# H41R70.net
KiCad netlist of a schematic drawn in EAGLE
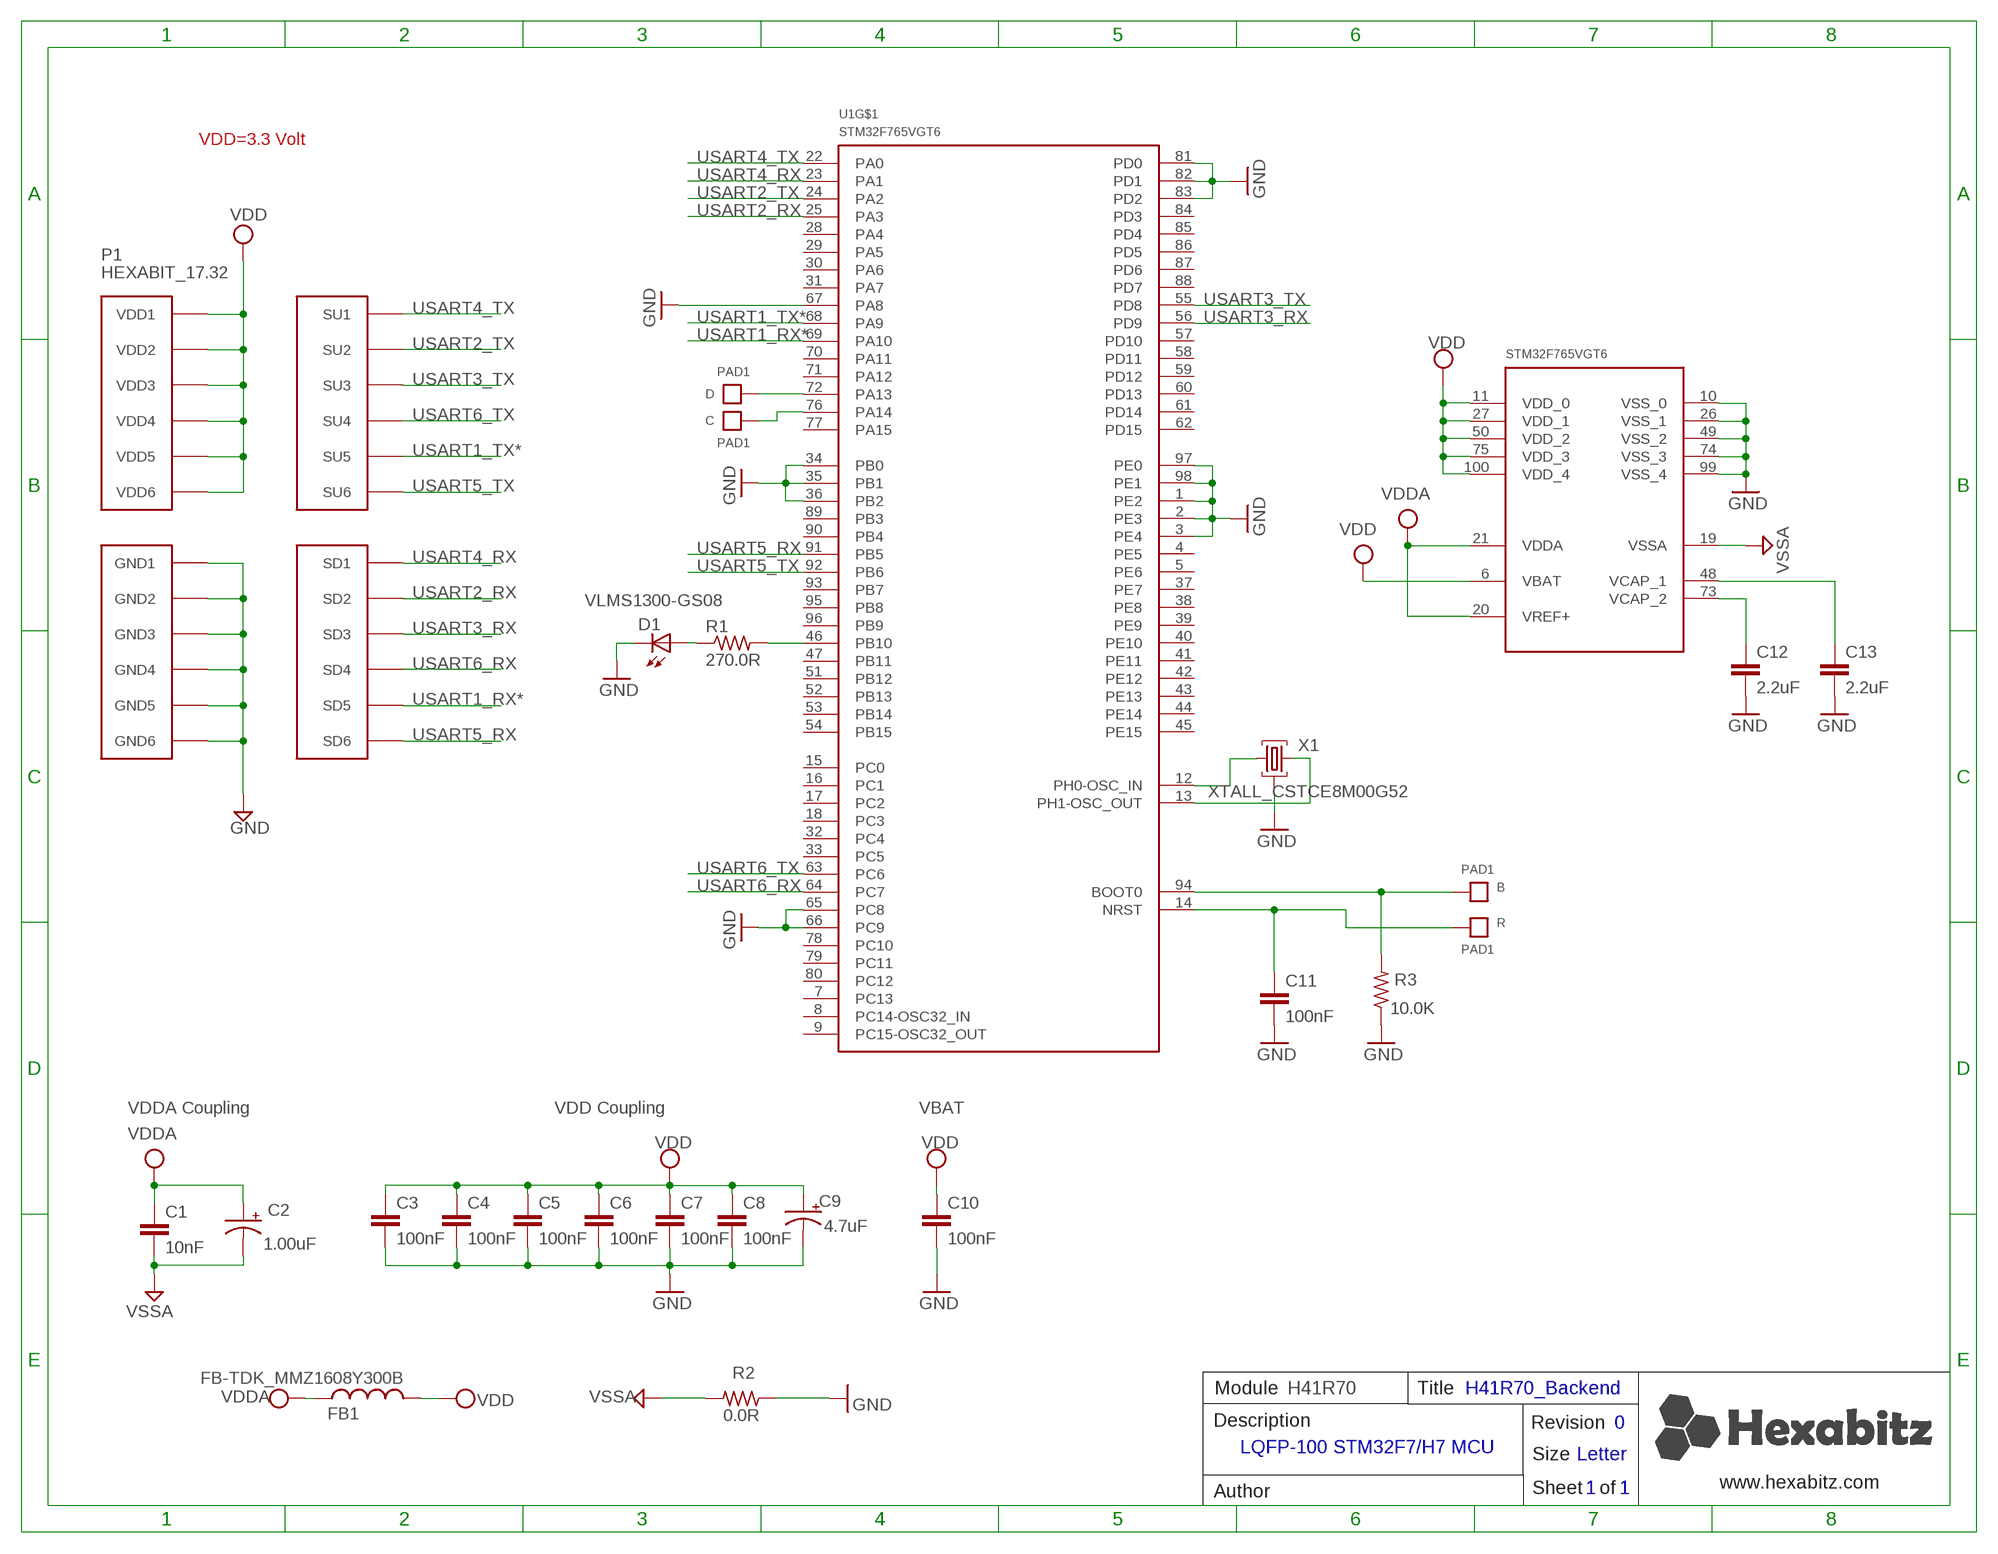
[diagram p0: schematic, sheet 1]

(export (version "E")
  (design (tool "Eeschema 10.0.6"))
  (components
    (comp (ref "B")
      (value "PAD1")
      (footprint "eagle-import:PAD1")
      (libsource (lib "eagle-import") (part "PAD1"))
    )
    (comp (ref "C")
      (value "PAD1")
      (footprint "eagle-import:PAD1")
      (libsource (lib "eagle-import") (part "PAD1"))
    )
    (comp (ref "C1")
      (value "10nF")
      (footprint "eagle-import:C-0603")
      (fields
        (field (name "CAPACITANCE") "10nF")
        (field (name "MFN") "KEMET")
        (field (name "MPN") "C0603C103K5RACTU")
        (field (name "OCTOPART_URL") "https://octopart.com/c0603c103k5ractu-kemet-133094?r=sp&s=R_iPBxLnSmGqhkU2rIMFpg")
        (field (name "TOLERANCE") "10%")
        (field (name "VOLTAGE_RATING") "50V")
      )
      (libsource (lib "eagle-import") (part "C-0603"))
    )
    (comp (ref "C2")
      (value "1.00uF")
      (footprint "eagle-import:C-0805-POL")
      (fields
        (field (name "CAPACITANCE") "1.00uF")
        (field (name "MFN") "Yageo")
        (field (name "MPN") "CC0805KKX7R7BB105")
        (field (name "OCTOPART_URL") "https://octopart.com/cc0805kkx7r7bb105-yageo-8376555?r=sp&s=YKl1wwtkROau_X5nniH2ig")
        (field (name "TOLERANCE") "10%")
        (field (name "VOLTAGE_RATING") "16V")
      )
      (libsource (lib "eagle-import") (part "C-0805-POL"))
    )
    (comp (ref "C3")
      (value "100nF")
      (footprint "eagle-import:C-0603")
      (fields
        (field (name "CAPACITANCE") "100nF")
        (field (name "MFN") "KEMET")
        (field (name "MPN") "C0603C104K8RACTU")
        (field (name "OCTOPART_URL") "https://octopart.com/c0603c104k8ractu-kemet-145075?r=sp&s=9bS9ASSwSEqMCE9KBEQZ0g")
        (field (name "TOLERANCE") "10%")
        (field (name "VOLTAGE_RATING") "10V")
      )
      (libsource (lib "eagle-import") (part "C-0603"))
    )
    (comp (ref "C4")
      (value "100nF")
      (footprint "eagle-import:C-0603")
      (fields
        (field (name "CAPACITANCE") "100nF")
        (field (name "MFN") "KEMET")
        (field (name "MPN") "C0603C104K8RACTU")
        (field (name "OCTOPART_URL") "https://octopart.com/c0603c104k8ractu-kemet-145075?r=sp&s=9bS9ASSwSEqMCE9KBEQZ0g")
        (field (name "TOLERANCE") "10%")
        (field (name "VOLTAGE_RATING") "10V")
      )
      (libsource (lib "eagle-import") (part "C-0603"))
    )
    (comp (ref "C5")
      (value "100nF")
      (footprint "eagle-import:C-0603")
      (fields
        (field (name "CAPACITANCE") "100nF")
        (field (name "MFN") "KEMET")
        (field (name "MPN") "C0603C104K8RACTU")
        (field (name "OCTOPART_URL") "https://octopart.com/c0603c104k8ractu-kemet-145075?r=sp&s=9bS9ASSwSEqMCE9KBEQZ0g")
        (field (name "TOLERANCE") "10%")
        (field (name "VOLTAGE_RATING") "10V")
      )
      (libsource (lib "eagle-import") (part "C-0603"))
    )
    (comp (ref "C6")
      (value "100nF")
      (footprint "eagle-import:C-0603")
      (fields
        (field (name "CAPACITANCE") "100nF")
        (field (name "MFN") "KEMET")
        (field (name "MPN") "C0603C104K8RACTU")
        (field (name "OCTOPART_URL") "https://octopart.com/c0603c104k8ractu-kemet-145075?r=sp&s=9bS9ASSwSEqMCE9KBEQZ0g")
        (field (name "TOLERANCE") "10%")
        (field (name "VOLTAGE_RATING") "10V")
      )
      (libsource (lib "eagle-import") (part "C-0603"))
    )
    (comp (ref "C7")
      (value "100nF")
      (footprint "eagle-import:C-0603")
      (fields
        (field (name "CAPACITANCE") "100nF")
        (field (name "MFN") "KEMET")
        (field (name "MPN") "C0603C104K8RACTU")
        (field (name "OCTOPART_URL") "https://octopart.com/c0603c104k8ractu-kemet-145075?r=sp&s=9bS9ASSwSEqMCE9KBEQZ0g")
        (field (name "TOLERANCE") "10%")
        (field (name "VOLTAGE_RATING") "10")
      )
      (libsource (lib "eagle-import") (part "C-0603"))
    )
    (comp (ref "C8")
      (value "100nF")
      (footprint "eagle-import:C-0603")
      (fields
        (field (name "CAPACITANCE") "100nF")
        (field (name "MFN") "KEMET")
        (field (name "MPN") "C0603C104K8RACTU")
        (field (name "OCTOPART_URL") "https://octopart.com/c0603c104k8ractu-kemet-145075?r=sp&s=9bS9ASSwSEqMCE9KBEQZ0g")
        (field (name "TOLERANCE") "10%")
        (field (name "VOLTAGE_RATING") "10V")
      )
      (libsource (lib "eagle-import") (part "C-0603"))
    )
    (comp (ref "C9")
      (value "4.7uF")
      (footprint "eagle-import:C-0805-POL")
      (fields
        (field (name "CAPACITANCE") "4.7uF")
        (field (name "MFN") "Murata")
        (field (name "MPN") "GRM21BC81E475KA12L")
        (field (name "OCTOPART_URL") "https://octopart.com/grm21bc81e475ka12l-murata-10331911?r=sp&s=RY3qZSD8T6mG6TC9CHI5qQ")
        (field (name "TOLERANCE") "10%")
        (field (name "VOLTAGE_RATING") "25V")
      )
      (libsource (lib "eagle-import") (part "C-0805-POL"))
    )
    (comp (ref "C10")
      (value "100nF")
      (footprint "eagle-import:C-0603")
      (fields
        (field (name "CAPACITANCE") "100nF")
        (field (name "MFN") "KEMET")
        (field (name "MPN") "C0603C104K8RACTU")
        (field (name "OCTOPART_URL") "https://octopart.com/c0603c104k8ractu-kemet-145075?r=sp&s=9bS9ASSwSEqMCE9KBEQZ0g")
        (field (name "TOLERANCE") "10V")
        (field (name "VOLTAGE_RATING") "10%")
      )
      (libsource (lib "eagle-import") (part "C-0603"))
    )
    (comp (ref "C11")
      (value "100nF")
      (footprint "eagle-import:C-0603")
      (fields
        (field (name "CAPACITANCE") "100nF")
        (field (name "MFN") "KEMET")
        (field (name "MPN") "C0603C104K8RACTU")
        (field (name "OCTOPART_URL") "https://octopart.com/c0603c104k8ractu-kemet-145075?r=sp&s=9bS9ASSwSEqMCE9KBEQZ0g")
        (field (name "TOLERANCE") "10%")
        (field (name "VOLTAGE_RATING") "10V")
      )
      (libsource (lib "eagle-import") (part "C-0603"))
    )
    (comp (ref "C12")
      (value "2.2uF")
      (footprint "eagle-import:C-0603")
      (fields
        (field (name "CAPACITANCE") "2.2uF")
        (field (name "MFN") "TDK Corporation")
        (field (name "MPN") "C1608X5R1C225K080AB")
        (field (name "OCTOPART_URL") "https://octopart.com/c1608x5r1c225k080ab-tdk-26013481?r=sp&s=zh0P7eqWSJSPxGSwstsLZg")
        (field (name "TOLERANCE") "16V")
        (field (name "VOLTAGE_RATING") "20%")
      )
      (libsource (lib "eagle-import") (part "C-0603"))
    )
    (comp (ref "C13")
      (value "2.2uF")
      (footprint "eagle-import:C-0603")
      (fields
        (field (name "CAPACITANCE") "2.2uF")
        (field (name "MFN") "TDK Corporation")
        (field (name "MPN") "C1608X5R1C225K080AB")
        (field (name "OCTOPART_URL") "https://octopart.com/c1608x5r1c225k080ab-tdk-26013481?r=sp&s=zh0P7eqWSJSPxGSwstsLZg")
        (field (name "TOLERANCE") "16V")
        (field (name "VOLTAGE_RATING") "20%")
      )
      (libsource (lib "eagle-import") (part "C-0603"))
    )
    (comp (ref "D")
      (value "PAD1")
      (footprint "eagle-import:PAD1")
      (libsource (lib "eagle-import") (part "PAD1"))
    )
    (comp (ref "D1")
      (value "VLMS1300-GS08")
      (footprint "eagle-import:VLMS1300-GS08")
      (fields
        (field (name "MFN") "Vishay")
        (field (name "MPN") "VLMS1300-GS08")
        (field (name "OCTOPART_URL") "https://octopart.com/vlms1300-gs08-vishay-21709201?r=sp&s=_gcP4_q8T1SC6PJQPTQ9yA")
      )
      (libsource (lib "eagle-import") (part "VLMS1300-GS08"))
    )
    (comp (ref "FB1")
      (value "FB-TDK_MMZ1608Y300B")
      (footprint "eagle-import:FB-TDK_MMZ1608Y300B")
      (fields
        (field (name "MFN") "TDK ")
        (field (name "MPN") "MMZ1608Y300B")
        (field (name "OCTOPART_URL") "https://octopart.com/mmz1608y300b-tdk-368280?r=sp&s=cd9_2ZEqQ9q9UNBuQgHAiA")
      )
      (libsource (lib "eagle-import") (part "FB-TDK_MMZ1608Y300B"))
    )
    (comp (ref "P1")
      (value "HEXABIT_17.32")
      (footprint "eagle-import:HEXABIT_17.32")
      (libsource (lib "eagle-import") (part "HEXABIT_?17.32"))
    )
    (comp (ref "R")
      (value "PAD1")
      (footprint "eagle-import:PAD1")
      (libsource (lib "eagle-import") (part "PAD1"))
    )
    (comp (ref "R1")
      (value "270.0R")
      (footprint "eagle-import:R-0603")
      (fields
        (field (name "MFN") "Yageo")
        (field (name "MPN") "RC0603FR-07270RL")
        (field (name "OCTOPART_URL") "https://octopart.com/search?q=RC0603FR-07270RL&start=0")
        (field (name "RESISTANCE") "270.0 Ohm")
        (field (name "TOLERANCE") "1%")
      )
      (libsource (lib "eagle-import") (part "R-0603"))
    )
    (comp (ref "R2")
      (value "0.0R")
      (footprint "eagle-import:R-0603")
      (fields
        (field (name "MFN") "Yageo")
        (field (name "MPN") "RC0603JR-070RL")
        (field (name "OCTOPART_URL") "https://octopart.com/rc0603jr-070rl-yageo-1241539?r=sp&s=X2NteqRjRNWrnx42Y0aliA")
        (field (name "RESISTANCE") "0.0 Ohm")
      )
      (libsource (lib "eagle-import") (part "R-0603"))
    )
    (comp (ref "R3")
      (value "10.0K")
      (footprint "eagle-import:R-0603")
      (fields
        (field (name "MFN") "Yageo")
        (field (name "MPN") "RC0603JR-0710KL")
        (field (name "OCTOPART_URL") "https://octopart.com/search?q=RC0603JR-0710KL&start=0")
        (field (name "RESISTANCE") "10.0K Ohm")
        (field (name "TOLERANCE") "5%")
      )
      (libsource (lib "eagle-import") (part "R-0603"))
    )
    (comp (ref "U1")
      (value "STM32F765VGT6")
      (footprint "eagle-import:LQFP-100")
      (libsource (lib "eagle-import") (part "STM32F765VGT6"))
    )
    (comp (ref "X1")
      (value "XTALL_CSTCE8M00G52")
      (footprint "eagle-import:XTALL_CSTCE8M00G52")
      (fields (field (name "MPN") "CSTCE8M00G52Z-R0"))
      (libsource (lib "eagle-import") (part "XTALL_CSTCE8M00G52"))
    )
  )
  (nets
    (net (code "1") (name "/USART1_RX*") (class "Default")
      (node (ref "P1") (pin "PAD_PD5") (pinfunction "SD5_PAD_PD5") (pintype "bidirectional"))
      (node (ref "U1") (pin "69") (pinfunction "PA10_69") (pintype "bidirectional"))
    )
    (net (code "2") (name "/USART1_TX*") (class "Default")
      (node (ref "P1") (pin "PAD_PU5") (pinfunction "SU5_PAD_PU5") (pintype "bidirectional"))
      (node (ref "U1") (pin "68") (pinfunction "PA9_68") (pintype "bidirectional"))
    )
    (net (code "3") (name "/USART2_RX") (class "Default")
      (node (ref "P1") (pin "PAD_PD2") (pinfunction "SD2_PAD_PD2") (pintype "bidirectional"))
      (node (ref "U1") (pin "25") (pinfunction "PA3_25") (pintype "bidirectional"))
    )
    (net (code "4") (name "/USART2_TX") (class "Default")
      (node (ref "P1") (pin "PAD_PU2") (pinfunction "SU2_PAD_PU2") (pintype "bidirectional"))
      (node (ref "U1") (pin "24") (pinfunction "PA2_24") (pintype "bidirectional"))
    )
    (net (code "5") (name "/USART3_RX") (class "Default")
      (node (ref "P1") (pin "PAD_PD3") (pinfunction "SD3_PAD_PD3") (pintype "bidirectional"))
      (node (ref "U1") (pin "56") (pinfunction "PD9_56") (pintype "bidirectional"))
    )
    (net (code "6") (name "/USART3_TX") (class "Default")
      (node (ref "P1") (pin "PAD_PU3") (pinfunction "SU3_PAD_PU3") (pintype "bidirectional"))
      (node (ref "U1") (pin "55") (pinfunction "PD8_55") (pintype "bidirectional"))
    )
    (net (code "7") (name "/USART4_RX") (class "Default")
      (node (ref "P1") (pin "PAD_PD1") (pinfunction "SD1_PAD_PD1") (pintype "bidirectional"))
      (node (ref "U1") (pin "23") (pinfunction "PA1_23") (pintype "bidirectional"))
    )
    (net (code "8") (name "/USART4_TX") (class "Default")
      (node (ref "P1") (pin "PAD_PU1") (pinfunction "SU1_PAD_PU1") (pintype "bidirectional"))
      (node (ref "U1") (pin "22") (pinfunction "PA0_22") (pintype "bidirectional"))
    )
    (net (code "9") (name "/USART5_RX") (class "Default")
      (node (ref "P1") (pin "PAD_PD6") (pinfunction "SD6_PAD_PD6") (pintype "bidirectional"))
      (node (ref "U1") (pin "91") (pinfunction "PB5_91") (pintype "bidirectional"))
    )
    (net (code "10") (name "/USART5_TX") (class "Default")
      (node (ref "P1") (pin "PAD_PU6") (pinfunction "SU6_PAD_PU6") (pintype "bidirectional"))
      (node (ref "U1") (pin "92") (pinfunction "PB6_92") (pintype "bidirectional"))
    )
    (net (code "11") (name "/USART6_RX") (class "Default")
      (node (ref "P1") (pin "PAD_PD4") (pinfunction "SD4_PAD_PD4") (pintype "bidirectional"))
      (node (ref "U1") (pin "64") (pinfunction "PC7_64") (pintype "bidirectional"))
    )
    (net (code "12") (name "/USART6_TX") (class "Default")
      (node (ref "P1") (pin "PAD_PU4") (pinfunction "SU4_PAD_PU4") (pintype "bidirectional"))
      (node (ref "U1") (pin "63") (pinfunction "PC6_63") (pintype "bidirectional"))
    )
    (net (code "13") (name "GND") (class "Default")
      (node (ref "C10") (pin "2") (pinfunction "2_2") (pintype "passive"))
      (node (ref "C11") (pin "2") (pinfunction "2_2") (pintype "passive"))
      (node (ref "C12") (pin "2") (pinfunction "2_2") (pintype "passive"))
      (node (ref "C13") (pin "2") (pinfunction "2_2") (pintype "passive"))
      (node (ref "C3") (pin "2") (pinfunction "2_2") (pintype "passive"))
      (node (ref "C4") (pin "2") (pinfunction "2_2") (pintype "passive"))
      (node (ref "C5") (pin "2") (pinfunction "2_2") (pintype "passive"))
      (node (ref "C6") (pin "2") (pinfunction "2_2") (pintype "passive"))
      (node (ref "C7") (pin "2") (pinfunction "2_2") (pintype "passive"))
      (node (ref "C8") (pin "2") (pinfunction "2_2") (pintype "passive"))
      (node (ref "C9") (pin "2") (pinfunction "-_2") (pintype "passive"))
      (node (ref "D1") (pin "C") (pinfunction "C_C") (pintype "passive"))
      (node (ref "P1") (pin "PAD_PD10") (pinfunction "GND4_PAD_PD10") (pintype "power_in"))
      (node (ref "P1") (pin "PAD_PD11") (pinfunction "GND5_PAD_PD11") (pintype "power_in"))
      (node (ref "P1") (pin "PAD_PD12") (pinfunction "GND6_PAD_PD12") (pintype "power_in"))
      (node (ref "P1") (pin "PAD_PD7") (pinfunction "GND1_PAD_PD7") (pintype "power_in"))
      (node (ref "P1") (pin "PAD_PD8") (pinfunction "GND2_PAD_PD8") (pintype "power_in"))
      (node (ref "P1") (pin "PAD_PD9") (pinfunction "GND3_PAD_PD9") (pintype "power_in"))
      (node (ref "R2") (pin "1") (pinfunction "1_1") (pintype "passive"))
      (node (ref "R3") (pin "1") (pinfunction "1_1") (pintype "passive"))
      (node (ref "U1") (pin "1") (pinfunction "PE2_1") (pintype "bidirectional"))
      (node (ref "U1") (pin "10") (pinfunction "VSS_0_10") (pintype "power_in"))
      (node (ref "U1") (pin "2") (pinfunction "PE3_2") (pintype "bidirectional"))
      (node (ref "U1") (pin "26") (pinfunction "VSS_1_26") (pintype "power_in"))
      (node (ref "U1") (pin "3") (pinfunction "PE4_3") (pintype "bidirectional"))
      (node (ref "U1") (pin "34") (pinfunction "PB0_34") (pintype "bidirectional"))
      (node (ref "U1") (pin "35") (pinfunction "PB1_35") (pintype "bidirectional"))
      (node (ref "U1") (pin "36") (pinfunction "PB2_36") (pintype "bidirectional"))
      (node (ref "U1") (pin "49") (pinfunction "VSS_2_49") (pintype "power_in"))
      (node (ref "U1") (pin "65") (pinfunction "PC8_65") (pintype "bidirectional"))
      (node (ref "U1") (pin "66") (pinfunction "PC9_66") (pintype "bidirectional"))
      (node (ref "U1") (pin "67") (pinfunction "PA8_67") (pintype "bidirectional"))
      (node (ref "U1") (pin "74") (pinfunction "VSS_3_74") (pintype "power_in"))
      (node (ref "U1") (pin "81") (pinfunction "PD0_81") (pintype "bidirectional"))
      (node (ref "U1") (pin "82") (pinfunction "PD1_82") (pintype "bidirectional"))
      (node (ref "U1") (pin "83") (pinfunction "PD2_83") (pintype "bidirectional"))
      (node (ref "U1") (pin "97") (pinfunction "PE0_97") (pintype "bidirectional"))
      (node (ref "U1") (pin "98") (pinfunction "PE1_98") (pintype "bidirectional"))
      (node (ref "U1") (pin "99") (pinfunction "VSS_4_99") (pintype "power_in"))
      (node (ref "X1") (pin "P$2") (pinfunction "2_P$2") (pintype "passive"))
    )
    (net (code "14") (name "Net-(D1-PadA)") (class "Default")
      (node (ref "D1") (pin "A") (pinfunction "A_A") (pintype "passive"))
      (node (ref "R1") (pin "1") (pinfunction "1_1") (pintype "passive"))
    )
    (net (code "15") (name "Net-(U1A-BOOT0)") (class "Default")
      (node (ref "B") (pin "P$1") (pinfunction "P$1_P$1") (pintype "passive"))
      (node (ref "B") (pin "P$2") (pinfunction "P$1_P$2") (pintype "passive"))
      (node (ref "R3") (pin "2") (pinfunction "2_2") (pintype "passive"))
      (node (ref "U1") (pin "94") (pinfunction "BOOT0_94") (pintype "input"))
    )
    (net (code "16") (name "Net-(U1A-NRST)") (class "Default")
      (node (ref "C11") (pin "1") (pinfunction "1_1") (pintype "passive"))
      (node (ref "R") (pin "P$1") (pinfunction "P$1_P$1") (pintype "passive"))
      (node (ref "R") (pin "P$2") (pinfunction "P$1_P$2") (pintype "passive"))
      (node (ref "U1") (pin "14") (pinfunction "NRST_14") (pintype "passive"))
    )
    (net (code "17") (name "Net-(U1A-PA13)") (class "Default")
      (node (ref "D") (pin "P$1") (pinfunction "P$1_P$1") (pintype "passive"))
      (node (ref "D") (pin "P$2") (pinfunction "P$1_P$2") (pintype "passive"))
      (node (ref "U1") (pin "72") (pinfunction "PA13_72") (pintype "bidirectional"))
    )
    (net (code "18") (name "Net-(U1A-PA14)") (class "Default")
      (node (ref "C") (pin "P$1") (pinfunction "P$1_P$1") (pintype "passive"))
      (node (ref "C") (pin "P$2") (pinfunction "P$1_P$2") (pintype "passive"))
      (node (ref "U1") (pin "76") (pinfunction "PA14_76") (pintype "bidirectional"))
    )
    (net (code "19") (name "Net-(U1A-PB10)") (class "Default")
      (node (ref "R1") (pin "2") (pinfunction "2_2") (pintype "passive"))
      (node (ref "U1") (pin "46") (pinfunction "PB10_46") (pintype "bidirectional"))
    )
    (net (code "20") (name "Net-(U1A-PH0-OSC_IN)") (class "Default")
      (node (ref "U1") (pin "12") (pinfunction "PH0-OSC_IN_12") (pintype "bidirectional"))
      (node (ref "X1") (pin "P$1") (pinfunction "1_P$1") (pintype "passive"))
    )
    (net (code "21") (name "Net-(U1A-PH1-OSC_OUT)") (class "Default")
      (node (ref "U1") (pin "13") (pinfunction "PH1-OSC_OUT_13") (pintype "bidirectional"))
      (node (ref "X1") (pin "P$3") (pinfunction "3_P$3") (pintype "passive"))
    )
    (net (code "22") (name "Net-(U1B-VCAP_1)") (class "Default")
      (node (ref "C13") (pin "1") (pinfunction "1_1") (pintype "passive"))
      (node (ref "U1") (pin "48") (pinfunction "VCAP_1_48") (pintype "power_in"))
    )
    (net (code "23") (name "Net-(U1B-VCAP_2)") (class "Default")
      (node (ref "C12") (pin "1") (pinfunction "1_1") (pintype "passive"))
      (node (ref "U1") (pin "73") (pinfunction "VCAP_2_73") (pintype "power_in"))
    )
    (net (code "24") (name "VDD") (class "Default")
      (node (ref "C10") (pin "1") (pinfunction "1_1") (pintype "passive"))
      (node (ref "C3") (pin "1") (pinfunction "1_1") (pintype "passive"))
      (node (ref "C4") (pin "1") (pinfunction "1_1") (pintype "passive"))
      (node (ref "C5") (pin "1") (pinfunction "1_1") (pintype "passive"))
      (node (ref "C6") (pin "1") (pinfunction "1_1") (pintype "passive"))
      (node (ref "C7") (pin "1") (pinfunction "1_1") (pintype "passive"))
      (node (ref "C8") (pin "1") (pinfunction "1_1") (pintype "passive"))
      (node (ref "C9") (pin "1") (pinfunction "+_1") (pintype "passive"))
      (node (ref "FB1") (pin "2") (pinfunction "2_2") (pintype "passive"))
      (node (ref "P1") (pin "PAD_PU10") (pinfunction "VDD4_PAD_PU10") (pintype "power_in"))
      (node (ref "P1") (pin "PAD_PU11") (pinfunction "VDD5_PAD_PU11") (pintype "power_in"))
      (node (ref "P1") (pin "PAD_PU12") (pinfunction "VDD6_PAD_PU12") (pintype "power_in"))
      (node (ref "P1") (pin "PAD_PU7") (pinfunction "VDD1_PAD_PU7") (pintype "power_in"))
      (node (ref "P1") (pin "PAD_PU8") (pinfunction "VDD2_PAD_PU8") (pintype "power_in"))
      (node (ref "P1") (pin "PAD_PU9") (pinfunction "VDD3_PAD_PU9") (pintype "power_in"))
      (node (ref "U1") (pin "100") (pinfunction "VDD_4_100") (pintype "power_in"))
      (node (ref "U1") (pin "11") (pinfunction "VDD_0_11") (pintype "power_in"))
      (node (ref "U1") (pin "27") (pinfunction "VDD_1_27") (pintype "power_in"))
      (node (ref "U1") (pin "50") (pinfunction "VDD_2_50") (pintype "power_in"))
      (node (ref "U1") (pin "6") (pinfunction "VBAT_6") (pintype "power_in"))
      (node (ref "U1") (pin "75") (pinfunction "VDD_3_75") (pintype "power_in"))
    )
    (net (code "25") (name "VDDA") (class "Default")
      (node (ref "C1") (pin "1") (pinfunction "1_1") (pintype "passive"))
      (node (ref "C2") (pin "1") (pinfunction "+_1") (pintype "passive"))
      (node (ref "FB1") (pin "1") (pinfunction "1_1") (pintype "passive"))
      (node (ref "U1") (pin "20") (pinfunction "VREF+_20") (pintype "power_in"))
      (node (ref "U1") (pin "21") (pinfunction "VDDA_21") (pintype "power_in"))
    )
    (net (code "26") (name "VSSA") (class "Default")
      (node (ref "C1") (pin "2") (pinfunction "2_2") (pintype "passive"))
      (node (ref "C2") (pin "2") (pinfunction "-_2") (pintype "passive"))
      (node (ref "R2") (pin "2") (pinfunction "2_2") (pintype "passive"))
      (node (ref "U1") (pin "19") (pinfunction "VSSA_19") (pintype "power_in"))
    )
    (net (code "27") (name "unconnected-(U1A-PA4-Pad28)") (class "Default")
      (node (ref "U1") (pin "28") (pinfunction "PA4_28") (pintype "bidirectional"))
    )
    (net (code "28") (name "unconnected-(U1A-PA5-Pad29)") (class "Default")
      (node (ref "U1") (pin "29") (pinfunction "PA5_29") (pintype "bidirectional"))
    )
    (net (code "29") (name "unconnected-(U1A-PA6-Pad30)") (class "Default")
      (node (ref "U1") (pin "30") (pinfunction "PA6_30") (pintype "bidirectional"))
    )
    (net (code "30") (name "unconnected-(U1A-PA7-Pad31)") (class "Default")
      (node (ref "U1") (pin "31") (pinfunction "PA7_31") (pintype "bidirectional"))
    )
    (net (code "31") (name "unconnected-(U1A-PA11-Pad70)") (class "Default")
      (node (ref "U1") (pin "70") (pinfunction "PA11_70") (pintype "bidirectional"))
    )
    (net (code "32") (name "unconnected-(U1A-PA12-Pad71)") (class "Default")
      (node (ref "U1") (pin "71") (pinfunction "PA12_71") (pintype "bidirectional"))
    )
    (net (code "33") (name "unconnected-(U1A-PA15-Pad77)") (class "Default")
      (node (ref "U1") (pin "77") (pinfunction "PA15_77") (pintype "bidirectional"))
    )
    (net (code "34") (name "unconnected-(U1A-PB3-Pad89)") (class "Default")
      (node (ref "U1") (pin "89") (pinfunction "PB3_89") (pintype "bidirectional"))
    )
    (net (code "35") (name "unconnected-(U1A-PB4-Pad90)") (class "Default")
      (node (ref "U1") (pin "90") (pinfunction "PB4_90") (pintype "bidirectional"))
    )
    (net (code "36") (name "unconnected-(U1A-PB7-Pad93)") (class "Default")
      (node (ref "U1") (pin "93") (pinfunction "PB7_93") (pintype "bidirectional"))
    )
    (net (code "37") (name "unconnected-(U1A-PB8-Pad95)") (class "Default")
      (node (ref "U1") (pin "95") (pinfunction "PB8_95") (pintype "bidirectional"))
    )
    (net (code "38") (name "unconnected-(U1A-PB9-Pad96)") (class "Default")
      (node (ref "U1") (pin "96") (pinfunction "PB9_96") (pintype "bidirectional"))
    )
    (net (code "39") (name "unconnected-(U1A-PB11-Pad47)") (class "Default")
      (node (ref "U1") (pin "47") (pinfunction "PB11_47") (pintype "bidirectional"))
    )
    (net (code "40") (name "unconnected-(U1A-PB12-Pad51)") (class "Default")
      (node (ref "U1") (pin "51") (pinfunction "PB12_51") (pintype "bidirectional"))
    )
    (net (code "41") (name "unconnected-(U1A-PB13-Pad52)") (class "Default")
      (node (ref "U1") (pin "52") (pinfunction "PB13_52") (pintype "bidirectional"))
    )
    (net (code "42") (name "unconnected-(U1A-PB14-Pad53)") (class "Default")
      (node (ref "U1") (pin "53") (pinfunction "PB14_53") (pintype "bidirectional"))
    )
    (net (code "43") (name "unconnected-(U1A-PB15-Pad54)") (class "Default")
      (node (ref "U1") (pin "54") (pinfunction "PB15_54") (pintype "bidirectional"))
    )
    (net (code "44") (name "unconnected-(U1A-PC0-Pad15)") (class "Default")
      (node (ref "U1") (pin "15") (pinfunction "PC0_15") (pintype "bidirectional"))
    )
    (net (code "45") (name "unconnected-(U1A-PC1-Pad16)") (class "Default")
      (node (ref "U1") (pin "16") (pinfunction "PC1_16") (pintype "bidirectional"))
    )
    (net (code "46") (name "unconnected-(U1A-PC2-Pad17)") (class "Default")
      (node (ref "U1") (pin "17") (pinfunction "PC2_17") (pintype "bidirectional"))
    )
    (net (code "47") (name "unconnected-(U1A-PC3-Pad18)") (class "Default")
      (node (ref "U1") (pin "18") (pinfunction "PC3_18") (pintype "bidirectional"))
    )
    (net (code "48") (name "unconnected-(U1A-PC4-Pad32)") (class "Default")
      (node (ref "U1") (pin "32") (pinfunction "PC4_32") (pintype "bidirectional"))
    )
    (net (code "49") (name "unconnected-(U1A-PC5-Pad33)") (class "Default")
      (node (ref "U1") (pin "33") (pinfunction "PC5_33") (pintype "bidirectional"))
    )
    (net (code "50") (name "unconnected-(U1A-PC10-Pad78)") (class "Default")
      (node (ref "U1") (pin "78") (pinfunction "PC10_78") (pintype "bidirectional"))
    )
    (net (code "51") (name "unconnected-(U1A-PC11-Pad79)") (class "Default")
      (node (ref "U1") (pin "79") (pinfunction "PC11_79") (pintype "bidirectional"))
    )
    (net (code "52") (name "unconnected-(U1A-PC12-Pad80)") (class "Default")
      (node (ref "U1") (pin "80") (pinfunction "PC12_80") (pintype "bidirectional"))
    )
    (net (code "53") (name "unconnected-(U1A-PC13-Pad7)") (class "Default")
      (node (ref "U1") (pin "7") (pinfunction "PC13_7") (pintype "bidirectional"))
    )
    (net (code "54") (name "unconnected-(U1A-PC14-OSC32_IN-Pad8)") (class "Default")
      (node (ref "U1") (pin "8") (pinfunction "PC14-OSC32_IN_8") (pintype "bidirectional"))
    )
    (net (code "55") (name "unconnected-(U1A-PC15-OSC32_OUT-Pad9)") (class "Default")
      (node (ref "U1") (pin "9") (pinfunction "PC15-OSC32_OUT_9") (pintype "bidirectional"))
    )
    (net (code "56") (name "unconnected-(U1A-PD3-Pad84)") (class "Default")
      (node (ref "U1") (pin "84") (pinfunction "PD3_84") (pintype "bidirectional"))
    )
    (net (code "57") (name "unconnected-(U1A-PD4-Pad85)") (class "Default")
      (node (ref "U1") (pin "85") (pinfunction "PD4_85") (pintype "bidirectional"))
    )
    (net (code "58") (name "unconnected-(U1A-PD5-Pad86)") (class "Default")
      (node (ref "U1") (pin "86") (pinfunction "PD5_86") (pintype "bidirectional"))
    )
    (net (code "59") (name "unconnected-(U1A-PD6-Pad87)") (class "Default")
      (node (ref "U1") (pin "87") (pinfunction "PD6_87") (pintype "bidirectional"))
    )
    (net (code "60") (name "unconnected-(U1A-PD7-Pad88)") (class "Default")
      (node (ref "U1") (pin "88") (pinfunction "PD7_88") (pintype "bidirectional"))
    )
    (net (code "61") (name "unconnected-(U1A-PD10-Pad57)") (class "Default")
      (node (ref "U1") (pin "57") (pinfunction "PD10_57") (pintype "bidirectional"))
    )
    (net (code "62") (name "unconnected-(U1A-PD11-Pad58)") (class "Default")
      (node (ref "U1") (pin "58") (pinfunction "PD11_58") (pintype "bidirectional"))
    )
    (net (code "63") (name "unconnected-(U1A-PD12-Pad59)") (class "Default")
      (node (ref "U1") (pin "59") (pinfunction "PD12_59") (pintype "bidirectional"))
    )
    (net (code "64") (name "unconnected-(U1A-PD13-Pad60)") (class "Default")
      (node (ref "U1") (pin "60") (pinfunction "PD13_60") (pintype "bidirectional"))
    )
    (net (code "65") (name "unconnected-(U1A-PD14-Pad61)") (class "Default")
      (node (ref "U1") (pin "61") (pinfunction "PD14_61") (pintype "bidirectional"))
    )
    (net (code "66") (name "unconnected-(U1A-PD15-Pad62)") (class "Default")
      (node (ref "U1") (pin "62") (pinfunction "PD15_62") (pintype "bidirectional"))
    )
    (net (code "67") (name "unconnected-(U1A-PE5-Pad4)") (class "Default")
      (node (ref "U1") (pin "4") (pinfunction "PE5_4") (pintype "bidirectional"))
    )
    (net (code "68") (name "unconnected-(U1A-PE6-Pad5)") (class "Default")
      (node (ref "U1") (pin "5") (pinfunction "PE6_5") (pintype "bidirectional"))
    )
    (net (code "69") (name "unconnected-(U1A-PE7-Pad37)") (class "Default")
      (node (ref "U1") (pin "37") (pinfunction "PE7_37") (pintype "bidirectional"))
    )
    (net (code "70") (name "unconnected-(U1A-PE8-Pad38)") (class "Default")
      (node (ref "U1") (pin "38") (pinfunction "PE8_38") (pintype "bidirectional"))
    )
    (net (code "71") (name "unconnected-(U1A-PE9-Pad39)") (class "Default")
      (node (ref "U1") (pin "39") (pinfunction "PE9_39") (pintype "bidirectional"))
    )
    (net (code "72") (name "unconnected-(U1A-PE10-Pad40)") (class "Default")
      (node (ref "U1") (pin "40") (pinfunction "PE10_40") (pintype "bidirectional"))
    )
    (net (code "73") (name "unconnected-(U1A-PE11-Pad41)") (class "Default")
      (node (ref "U1") (pin "41") (pinfunction "PE11_41") (pintype "bidirectional"))
    )
    (net (code "74") (name "unconnected-(U1A-PE12-Pad42)") (class "Default")
      (node (ref "U1") (pin "42") (pinfunction "PE12_42") (pintype "bidirectional"))
    )
    (net (code "75") (name "unconnected-(U1A-PE13-Pad43)") (class "Default")
      (node (ref "U1") (pin "43") (pinfunction "PE13_43") (pintype "bidirectional"))
    )
    (net (code "76") (name "unconnected-(U1A-PE14-Pad44)") (class "Default")
      (node (ref "U1") (pin "44") (pinfunction "PE14_44") (pintype "bidirectional"))
    )
    (net (code "77") (name "unconnected-(U1A-PE15-Pad45)") (class "Default")
      (node (ref "U1") (pin "45") (pinfunction "PE15_45") (pintype "bidirectional"))
    )
  )
)
